# PowerAmp.net
KiCad netlist of a schematic drawn in Altium Designer
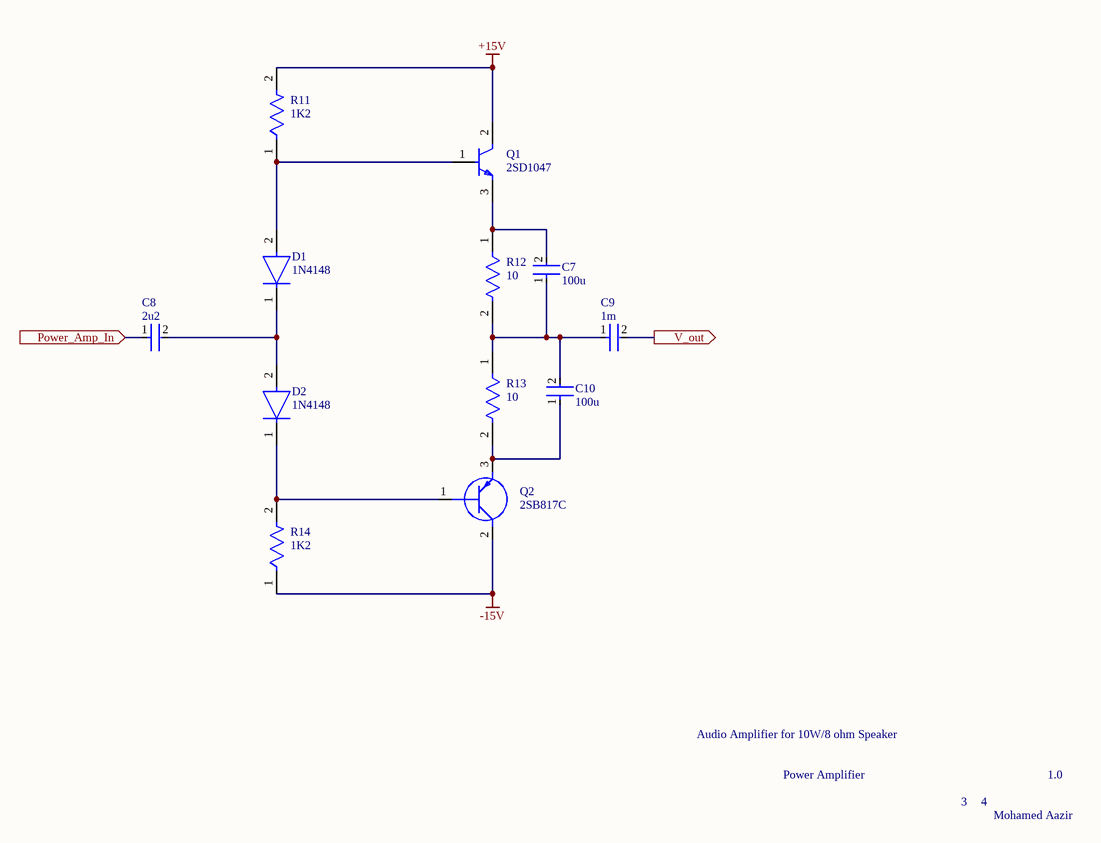
[diagram p0: PowerAmp.SchDoc]

(export (version "E")
  (design (tool "Eeschema 10.0.6"))
  (components
    (comp (ref "C7")
      (value "100u")
      (footprint "FP-RAD-TH-D_5_0_5-L_11_1-MFG")
      (description "Aluminum Electrolytic Capacitors (Radial Lead Type) 22uF ±20% 25V")
      (fields (field (name "TOLERANCE") "20%") (field (name "VOLTAGE") "25V"))
      (libsource (lib "Altium Content Vault") (part "b4654b650e69147ec39a6b967a45e02"))
    )
    (comp (ref "C8")
      (value "2u2")
      (footprint "FP-RAD-TH-D_5_0_5-L_11_1-MFG")
      (description "Aluminum Electrolytic Capacitors (Radial Lead Type) 22uF ±20% 25V")
      (fields (field (name "TOLERANCE") "20%") (field (name "VOLTAGE") "25V"))
      (libsource (lib "Altium Content Vault") (part "b4654b650e69147ec39a6b967a45e02"))
    )
    (comp (ref "C9")
      (value "1m")
      (footprint "FP-RAD-TH-D_5_0_5-L_11_1-MFG")
      (description "Aluminum Electrolytic Capacitors (Radial Lead Type) 22uF ±20% 25V")
      (fields (field (name "TOLERANCE") "20%") (field (name "VOLTAGE") "25V"))
      (libsource (lib "Altium Content Vault") (part "b4654b650e69147ec39a6b967a45e02"))
    )
    (comp (ref "C10")
      (value "100u")
      (footprint "FP-RAD-TH-D_5_0_5-L_11_1-MFG")
      (description "Aluminum Electrolytic Capacitors (Radial Lead Type) 22uF ±20% 25V")
      (fields (field (name "TOLERANCE") "20%") (field (name "VOLTAGE") "25V"))
      (libsource (lib "Altium Content Vault") (part "b4654b650e69147ec39a6b967a45e02"))
    )
    (comp (ref "D1")
      (value "1N4148")
      (footprint "FP-017AG-MFG")
      (description "DIODE GEN PURP 100V 200MA DO35")
      (fields (field (name "VOLTAGE") "100V"))
      (libsource (lib "Altium Content Vault") (part "d7152d700b627762746794eb795d46e"))
    )
    (comp (ref "D2")
      (value "1N4148")
      (footprint "FP-017AG-MFG")
      (description "DIODE GEN PURP 100V 200MA DO35")
      (fields (field (name "VOLTAGE") "100V"))
      (libsource (lib "Altium Content Vault") (part "d7152d700b627762746794eb795d46e"))
    )
    (comp (ref "Q1")
      (value "2SD1047")
      (footprint "FP-2SD1047-MFG")
      (description "TRANS NPN 140V 12A TO-3P")
      (libsource (lib "Altium Content Vault") (part "1c57d9dae74fe2702546667b0e849db"))
    )
    (comp (ref "Q2")
      (value "2SB817C")
      (footprint "SamacSys:TO545P500X1560X2380-3P")
      (description "Transistor BJT PNP")
      (libsource (lib "*") (part "2SB817C"))
    )
    (comp (ref "R11")
      (value "1K2")
      (footprint "FP-MFR-25-MFG")
      (description "RES 1.18K OHM 1/4W 1% AXIAL")
      (fields (field (name "MANUFACTURER") "Yageo") (field (name "TOLERANCE") "1%"))
      (libsource (lib "Altium Content Vault") (part "1029c3af85768c4190bb7ad29bc67b5"))
    )
    (comp (ref "R12")
      (value "10")
      (footprint "FP-HVR37-MFG")
      (fields (field (name "TOLERANCE") "1%"))
      (libsource (lib "Altium Content Vault") (part "1029c3af85768c4190bb7ad29bc67b5"))
    )
    (comp (ref "R13")
      (value "10")
      (footprint "FP-HVR37-MFG")
      (fields (field (name "TOLERANCE") "1%"))
      (libsource (lib "Altium Content Vault") (part "1029c3af85768c4190bb7ad29bc67b5"))
    )
    (comp (ref "R14")
      (value "1K2")
      (footprint "FP-MFR-25-MFG")
      (description "RES 1.18K OHM 1/4W 1% AXIAL")
      (fields (field (name "MANUFACTURER") "Yageo") (field (name "TOLERANCE") "1%"))
      (libsource (lib "Altium Content Vault") (part "1029c3af85768c4190bb7ad29bc67b5"))
    )
  )
  (nets
    (net (code "1") (name "+15V") (class "Default")
      (node (ref "Q1") (pin "2") (pinfunction "C_2") (pintype "passive"))
      (node (ref "R11") (pin "2") (pinfunction "2_2") (pintype "passive"))
    )
    (net (code "2") (name "-15V") (class "Default")
      (node (ref "Q2") (pin "2") (pinfunction "C_2") (pintype "passive"))
      (node (ref "R14") (pin "1") (pinfunction "1_1") (pintype "passive"))
    )
    (net (code "3") (name "/Power_Amp_In") (class "Default")
      (node (ref "C8") (pin "1") (pinfunction "1_1") (pintype "passive"))
    )
    (net (code "4") (name "/V_out") (class "Default")
      (node (ref "C9") (pin "2") (pinfunction "2_2") (pintype "passive"))
    )
    (net (code "5") (name "Net-(C10-Pad2)") (class "Default")
      (node (ref "C10") (pin "2") (pinfunction "2_2") (pintype "passive"))
      (node (ref "C7") (pin "1") (pinfunction "1_1") (pintype "passive"))
      (node (ref "C9") (pin "1") (pinfunction "1_1") (pintype "passive"))
      (node (ref "R12") (pin "2") (pinfunction "2_2") (pintype "passive"))
      (node (ref "R13") (pin "1") (pinfunction "1_1") (pintype "passive"))
    )
    (net (code "6") (name "Net-(D1-A)") (class "Default")
      (node (ref "D1") (pin "2") (pinfunction "A_2") (pintype "passive"))
      (node (ref "Q1") (pin "1") (pinfunction "B_1") (pintype "passive"))
      (node (ref "R11") (pin "1") (pinfunction "1_1") (pintype "passive"))
    )
    (net (code "7") (name "Net-(D1-C)") (class "Default")
      (node (ref "C8") (pin "2") (pinfunction "2_2") (pintype "passive"))
      (node (ref "D1") (pin "1") (pinfunction "C_1") (pintype "passive"))
      (node (ref "D2") (pin "2") (pinfunction "A_2") (pintype "passive"))
    )
    (net (code "8") (name "Net-(D2-C)") (class "Default")
      (node (ref "D2") (pin "1") (pinfunction "C_1") (pintype "passive"))
      (node (ref "Q2") (pin "1") (pinfunction "B_1") (pintype "passive"))
      (node (ref "R14") (pin "2") (pinfunction "2_2") (pintype "passive"))
    )
    (net (code "9") (name "Net-(Q1-E)") (class "Default")
      (node (ref "C7") (pin "2") (pinfunction "2_2") (pintype "passive"))
      (node (ref "Q1") (pin "3") (pinfunction "E_3") (pintype "passive"))
      (node (ref "R12") (pin "1") (pinfunction "1_1") (pintype "passive"))
    )
    (net (code "10") (name "Net-(Q2-E)") (class "Default")
      (node (ref "C10") (pin "1") (pinfunction "1_1") (pintype "passive"))
      (node (ref "Q2") (pin "3") (pinfunction "E_3") (pintype "passive"))
      (node (ref "R13") (pin "2") (pinfunction "2_2") (pintype "passive"))
    )
  )
)
